# Mcu.net
KiCad netlist of a schematic drawn in Altium Designer
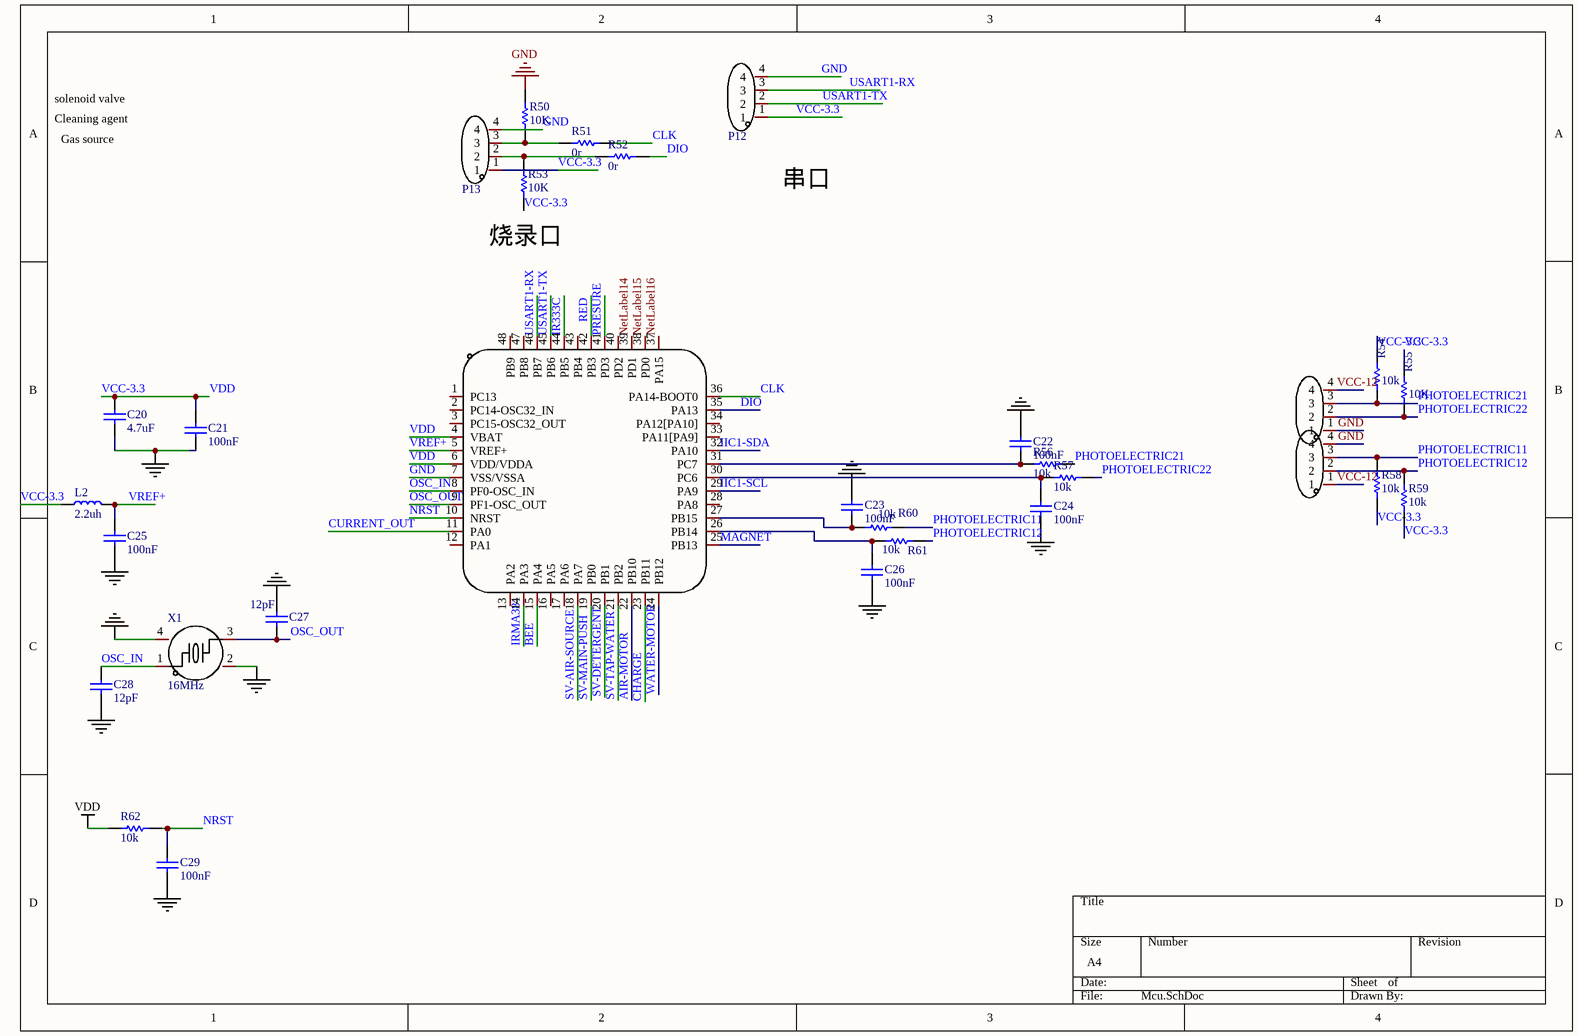
[diagram p0: Mcu.SchDoc]

(export (version "E")
  (design (tool "Eeschema 10.0.6"))
  (components
    (comp (ref "C20")
      (value "4.7uF")
      (footprint "zq:C0402")
      (fields (field (name "Comment") "CL05A475MP5NRNC") (field (name "PUBLISHER") "Altium Limited"))
      (libsource (lib "zq") (part "4.7uf"))
    )
    (comp (ref "C21")
      (value "100nF")
      (footprint "zq:C0402")
      (fields (field (name "Comment") "CL05B104KB54PNC") (field (name "PUBLISHER") "Altium Limited"))
      (libsource (lib "zq") (part "100nf"))
    )
    (comp (ref "C22")
      (value "100nF")
      (footprint "zq:C0402")
      (fields (field (name "Comment") "CL05B104KB54PNC") (field (name "PUBLISHER") "Altium Limited"))
      (libsource (lib "zq") (part "100nf"))
    )
    (comp (ref "C23")
      (value "100nF")
      (footprint "zq:C0402")
      (fields (field (name "Comment") "CL05B104KB54PNC") (field (name "PUBLISHER") "Altium Limited"))
      (libsource (lib "zq") (part "100nf"))
    )
    (comp (ref "C24")
      (value "100nF")
      (footprint "zq:C0402")
      (fields (field (name "Comment") "CL05B104KB54PNC") (field (name "PUBLISHER") "Altium Limited"))
      (libsource (lib "zq") (part "100nf"))
    )
    (comp (ref "C25")
      (value "100nF")
      (footprint "zq:C0402")
      (fields (field (name "Comment") "CL05B104KB54PNC") (field (name "PUBLISHER") "Altium Limited"))
      (libsource (lib "zq") (part "100nf"))
    )
    (comp (ref "C26")
      (value "100nF")
      (footprint "zq:C0402")
      (fields (field (name "Comment") "CL05B104KB54PNC") (field (name "PUBLISHER") "Altium Limited"))
      (libsource (lib "zq") (part "100nf"))
    )
    (comp (ref "C27")
      (value "12pF")
      (footprint "zq:C0402")
      (description "Capacitor")
      (fields (field (name "Comment") "0402CG120J500NT") (field (name "PUBLISHER") "Altium Limited"))
      (libsource (lib "zq") (part "cap"))
    )
    (comp (ref "C28")
      (value "12pF")
      (footprint "zq:C0402")
      (description "Capacitor")
      (fields (field (name "Comment") "0402CG120J500NT") (field (name "PUBLISHER") "Altium Limited"))
      (libsource (lib "zq") (part "cap"))
    )
    (comp (ref "C29")
      (value "100nF")
      (footprint "zq:C0402")
      (fields (field (name "Comment") "CL05B104KB54PNC") (field (name "PUBLISHER") "Altium Limited"))
      (libsource (lib "zq") (part "100nf"))
    )
    (comp (ref "L2")
      (value "2.2uh")
      (footprint "zq:L0603")
      (description "电感")
      (fields (field (name "Comment") "CMI160808U2R2KT"))
      (libsource (lib "zq") (part "inductance_small"))
    )
    (comp (ref "P12")
      (value "YTC-HAA200A-4A")
      (footprint "zq:CONN-TH_4P-P2.00_HCTL_HC-PH-4A-X")
      (description "4p")
      (fields (field (name "MANUFACTURER") "YIYUAN(怡远)"))
      (libsource (lib "zq") (part "ph 2.0"))
    )
    (comp (ref "P13")
      (value "YTC-HAA200A-4A")
      (footprint "zq:CONN-TH_4P-P2.00_HCTL_HC-PH-4A-X")
      (description "4p")
      (fields (field (name "MANUFACTURER") "YIYUAN(怡远)"))
      (libsource (lib "zq") (part "ph 2.0"))
    )
    (comp (ref "P14")
      (value "ZX-HY2.0-4PZZ")
      (footprint "zq:CONN-TH_4P-P2.00_HX20020-4A_2")
      (description "4p")
      (fields (field (name "MANUFACTURER") "Megastar(兆星)"))
      (libsource (lib "zq") (part "HY2.0-4PZZ"))
    )
    (comp (ref "P15")
      (value "ZX-HY2.0-4PZZ")
      (footprint "zq:CONN-TH_4P-P2.00_HX20020-4A_2")
      (description "4p")
      (fields (field (name "MANUFACTURER") "Megastar(兆星)"))
      (libsource (lib "zq") (part "HY2.0-4PZZ"))
    )
    (comp (ref "R50")
      (value "10K")
      (footprint "zq:R0402")
      (description "Semiconductor Resistor")
      (fields (field (name "Comment") "0402WGF1002TCE") (field (name "PUBLISHER") "Altium Limited"))
      (libsource (lib "zq") (part "10K"))
    )
    (comp (ref "R51")
      (value "0r")
      (footprint "zq:R0402")
      (fields (field (name "Comment") "0402WGF0000TCE") (field (name "PUBLISHER") "Altium Limited"))
      (libsource (lib "zq") (part "0r"))
    )
    (comp (ref "R52")
      (value "0r")
      (footprint "zq:R0402")
      (fields (field (name "Comment") "0402WGF0000TCE") (field (name "PUBLISHER") "Altium Limited"))
      (libsource (lib "zq") (part "0r"))
    )
    (comp (ref "R53")
      (value "10K")
      (footprint "zq:R0402")
      (description "Semiconductor Resistor")
      (fields (field (name "Comment") "0402WGF1002TCE") (field (name "PUBLISHER") "Altium Limited"))
      (libsource (lib "zq") (part "10K"))
    )
    (comp (ref "R54")
      (value "10k")
      (footprint "zq:R0402")
      (description "Semiconductor Resistor")
      (fields (field (name "Comment") "0402WGF1002TCE") (field (name "PUBLISHER") "Altium Limited"))
      (libsource (lib "zq") (part "Res Semi"))
    )
    (comp (ref "R55")
      (value "10K")
      (footprint "zq:R0402")
      (description "Semiconductor Resistor")
      (fields (field (name "Comment") "0402WGF1002TCE") (field (name "PUBLISHER") "Altium Limited"))
      (libsource (lib "zq") (part "Res Semi"))
    )
    (comp (ref "R56")
      (value "10k")
      (footprint "zq:R0402")
      (description "Semiconductor Resistor")
      (fields (field (name "Comment") "0402WGF1002TCE") (field (name "PUBLISHER") "Altium Limited"))
      (libsource (lib "zq") (part "Res Semi"))
    )
    (comp (ref "R57")
      (value "10k")
      (footprint "zq:R0402")
      (description "Semiconductor Resistor")
      (fields (field (name "Comment") "0402WGF1002TCE") (field (name "PUBLISHER") "Altium Limited"))
      (libsource (lib "zq") (part "Res Semi"))
    )
    (comp (ref "R58")
      (value "10k")
      (footprint "zq:R0402")
      (description "Semiconductor Resistor")
      (fields (field (name "Comment") "0402WGF1002TCE") (field (name "PUBLISHER") "Altium Limited"))
      (libsource (lib "zq") (part "Res Semi"))
    )
    (comp (ref "R59")
      (value "10k")
      (footprint "zq:R0402")
      (description "Semiconductor Resistor")
      (fields (field (name "Comment") "0402WGF1002TCE") (field (name "PUBLISHER") "Altium Limited"))
      (libsource (lib "zq") (part "Res Semi"))
    )
    (comp (ref "R60")
      (value "10k")
      (footprint "zq:R0402")
      (description "Semiconductor Resistor")
      (fields (field (name "Comment") "0402WGF1002TCE") (field (name "PUBLISHER") "Altium Limited"))
      (libsource (lib "zq") (part "Res Semi"))
    )
    (comp (ref "R61")
      (value "10k")
      (footprint "zq:R0402")
      (description "Semiconductor Resistor")
      (fields (field (name "Comment") "0402WGF1002TCE") (field (name "PUBLISHER") "Altium Limited"))
      (libsource (lib "zq") (part "Res Semi"))
    )
    (comp (ref "R62")
      (value "10k")
      (footprint "zq:R0402")
      (description "Semiconductor Resistor")
      (fields (field (name "Comment") "0402WGF1002TCE") (field (name "PUBLISHER") "Altium Limited"))
      (libsource (lib "zq") (part "Res Semi"))
    )
    (comp (ref "U4")
      (value "STM32G070CBT6")
      (footprint "zq:LQFP-48_L7.0-W7.0-P0.50-LS9.0-BL")
      (fields (field (name "MANUFACTURER") "ST(意法半导体)"))
      (libsource (lib "zq") (part "STM32G070CBT6"))
    )
    (comp (ref "X1")
      (value "X322516MLB4SI")
      (footprint "zq:CRYSTAL-SMD_4P-L3.2-W2.5-BL")
      (fields
        (field (name "MANUFACTURER") "YXC(扬兴晶振)")
        (field (name "MANUFACTURER PART") "XL7EL89COI-111YLC-16M")
        (field (name "NAME") "16MHz")
      )
      (libsource (lib "zq") (part "XL7EL89COI-111YLC-16M"))
    )
  )
  (nets
    (net (code "1") (name "/AIR-MOTOR") (class "Default")
      (node (ref "U4") (pin "22") (pinfunction "PB10_22") (pintype "passive"))
    )
    (net (code "2") (name "/BEE") (class "Default")
      (node (ref "U4") (pin "15") (pinfunction "PA4_15") (pintype "passive"))
    )
    (net (code "3") (name "/CHARGE") (class "Default")
      (node (ref "U4") (pin "23") (pinfunction "PB11_23") (pintype "passive"))
    )
    (net (code "4") (name "/CLK") (class "Default")
      (node (ref "R51") (pin "2") (pinfunction "2_2") (pintype "passive"))
      (node (ref "U4") (pin "36") (pinfunction "PA14-BOOT0_36") (pintype "passive"))
    )
    (net (code "5") (name "/CURRENT_OUT") (class "Default")
      (node (ref "U4") (pin "11") (pinfunction "PA0_11") (pintype "passive"))
    )
    (net (code "6") (name "/DIO") (class "Default")
      (node (ref "R52") (pin "2") (pinfunction "2_2") (pintype "passive"))
      (node (ref "U4") (pin "35") (pinfunction "PA13_35") (pintype "passive"))
    )
    (net (code "7") (name "/IIC1-SCL") (class "Default")
      (node (ref "U4") (pin "29") (pinfunction "PA9_29") (pintype "passive"))
    )
    (net (code "8") (name "/IIC1-SDA") (class "Default")
      (node (ref "U4") (pin "32") (pinfunction "PA10_32") (pintype "passive"))
    )
    (net (code "9") (name "/IR333C") (class "Default")
      (node (ref "U4") (pin "44") (pinfunction "PB5_44") (pintype "passive"))
    )
    (net (code "10") (name "/IRMA381") (class "Default")
      (node (ref "U4") (pin "14") (pinfunction "PA3_14") (pintype "passive"))
    )
    (net (code "11") (name "/MAGNET") (class "Default")
      (node (ref "U4") (pin "25") (pinfunction "PB13_25") (pintype "passive"))
    )
    (net (code "12") (name "/NRST") (class "Default")
      (node (ref "C29") (pin "1") (pinfunction "1_1") (pintype "passive"))
      (node (ref "R62") (pin "1") (pinfunction "1_1") (pintype "passive"))
      (node (ref "U4") (pin "10") (pinfunction "NRST_10") (pintype "passive"))
    )
    (net (code "13") (name "/NetLabel14") (class "Default")
      (node (ref "U4") (pin "39") (pinfunction "PD1_39") (pintype "passive"))
    )
    (net (code "14") (name "/NetLabel15") (class "Default")
      (node (ref "U4") (pin "38") (pinfunction "PD0_38") (pintype "passive"))
    )
    (net (code "15") (name "/NetLabel16") (class "Default")
      (node (ref "U4") (pin "37") (pinfunction "PA15_37") (pintype "passive"))
    )
    (net (code "16") (name "/OSC_IN") (class "Default")
      (node (ref "C28") (pin "2") (pinfunction "2_2") (pintype "passive"))
      (node (ref "U4") (pin "8") (pinfunction "PF0-OSC_IN_8") (pintype "passive"))
      (node (ref "X1") (pin "1") (pinfunction "1_1") (pintype "passive"))
    )
    (net (code "17") (name "/OSC_OUT") (class "Default")
      (node (ref "C27") (pin "1") (pinfunction "1_1") (pintype "passive"))
      (node (ref "U4") (pin "9") (pinfunction "PF1-OSC_OUT_9") (pintype "passive"))
      (node (ref "X1") (pin "3") (pinfunction "3_3") (pintype "passive"))
    )
    (net (code "18") (name "/PHOTOELECTRIC11") (class "Default")
      (node (ref "P15") (pin "3") (pinfunction "3_3") (pintype "passive"))
      (node (ref "R58") (pin "2") (pinfunction "2_2") (pintype "passive"))
      (node (ref "R60") (pin "2") (pinfunction "2_2") (pintype "passive"))
    )
    (net (code "19") (name "/PHOTOELECTRIC12") (class "Default")
      (node (ref "P15") (pin "2") (pinfunction "2_2") (pintype "passive"))
      (node (ref "R59") (pin "2") (pinfunction "2_2") (pintype "passive"))
      (node (ref "R61") (pin "2") (pinfunction "2_2") (pintype "passive"))
    )
    (net (code "20") (name "/PHOTOELECTRIC21") (class "Default")
      (node (ref "P14") (pin "3") (pinfunction "3_3") (pintype "passive"))
      (node (ref "R54") (pin "2") (pinfunction "2_2") (pintype "passive"))
      (node (ref "R56") (pin "2") (pinfunction "2_2") (pintype "passive"))
    )
    (net (code "21") (name "/PHOTOELECTRIC22") (class "Default")
      (node (ref "P14") (pin "2") (pinfunction "2_2") (pintype "passive"))
      (node (ref "R55") (pin "2") (pinfunction "2_2") (pintype "passive"))
      (node (ref "R57") (pin "2") (pinfunction "2_2") (pintype "passive"))
    )
    (net (code "22") (name "/PRESURE") (class "Default")
      (node (ref "U4") (pin "41") (pinfunction "PD3_41") (pintype "passive"))
    )
    (net (code "23") (name "/RED") (class "Default")
      (node (ref "U4") (pin "42") (pinfunction "PB3_42") (pintype "passive"))
    )
    (net (code "24") (name "/SV-AIR-SOURCE") (class "Default")
      (node (ref "U4") (pin "18") (pinfunction "PA7_18") (pintype "passive"))
    )
    (net (code "25") (name "/SV-DETERGENT") (class "Default")
      (node (ref "U4") (pin "20") (pinfunction "PB1_20") (pintype "passive"))
    )
    (net (code "26") (name "/SV-MAIN-PUSH") (class "Default")
      (node (ref "U4") (pin "19") (pinfunction "PB0_19") (pintype "passive"))
    )
    (net (code "27") (name "/SV-TAP-WATER") (class "Default")
      (node (ref "U4") (pin "21") (pinfunction "PB2_21") (pintype "passive"))
    )
    (net (code "28") (name "/USART1-RX") (class "Default")
      (node (ref "P12") (pin "3") (pinfunction "3_3") (pintype "passive"))
      (node (ref "U4") (pin "46") (pinfunction "PB7_46") (pintype "passive"))
    )
    (net (code "29") (name "/USART1-TX") (class "Default")
      (node (ref "P12") (pin "2") (pinfunction "2_2") (pintype "passive"))
      (node (ref "U4") (pin "45") (pinfunction "PB6_45") (pintype "passive"))
    )
    (net (code "30") (name "/VCC-12") (class "Default")
      (node (ref "P14") (pin "4") (pinfunction "4_4") (pintype "passive"))
      (node (ref "P15") (pin "1") (pinfunction "1_1") (pintype "passive"))
    )
    (net (code "31") (name "/VREF+") (class "Default")
      (node (ref "C25") (pin "1") (pinfunction "1_1") (pintype "passive"))
      (node (ref "L2") (pin "2") (pinfunction "2_2") (pintype "passive"))
      (node (ref "U4") (pin "5") (pinfunction "VREF+_5") (pintype "passive"))
    )
    (net (code "32") (name "/WATER-MOTOR") (class "Default")
      (node (ref "U4") (pin "24") (pinfunction "PB12_24") (pintype "passive"))
    )
    (net (code "33") (name "GND") (class "Default")
      (node (ref "C20") (pin "2") (pinfunction "2_2") (pintype "passive"))
      (node (ref "C21") (pin "2") (pinfunction "2_2") (pintype "passive"))
      (node (ref "C22") (pin "1") (pinfunction "1_1") (pintype "passive"))
      (node (ref "C23") (pin "1") (pinfunction "1_1") (pintype "passive"))
      (node (ref "C24") (pin "2") (pinfunction "2_2") (pintype "passive"))
      (node (ref "C25") (pin "2") (pinfunction "2_2") (pintype "passive"))
      (node (ref "C26") (pin "2") (pinfunction "2_2") (pintype "passive"))
      (node (ref "C27") (pin "2") (pinfunction "2_2") (pintype "passive"))
      (node (ref "C28") (pin "1") (pinfunction "1_1") (pintype "passive"))
      (node (ref "C29") (pin "2") (pinfunction "2_2") (pintype "passive"))
      (node (ref "P12") (pin "4") (pinfunction "4_4") (pintype "passive"))
      (node (ref "P13") (pin "4") (pinfunction "4_4") (pintype "passive"))
      (node (ref "P14") (pin "1") (pinfunction "1_1") (pintype "passive"))
      (node (ref "P15") (pin "4") (pinfunction "4_4") (pintype "passive"))
      (node (ref "R50") (pin "2") (pinfunction "2_2") (pintype "passive"))
      (node (ref "U4") (pin "7") (pinfunction "VSS/VSSA_7") (pintype "passive"))
      (node (ref "X1") (pin "2") (pinfunction "GND_2") (pintype "passive"))
      (node (ref "X1") (pin "4") (pinfunction "GND_4") (pintype "passive"))
    )
    (net (code "34") (name "Net-(P13-Pad2)") (class "Default")
      (node (ref "P13") (pin "2") (pinfunction "2_2") (pintype "passive"))
      (node (ref "R52") (pin "1") (pinfunction "1_1") (pintype "passive"))
      (node (ref "R53") (pin "2") (pinfunction "2_2") (pintype "passive"))
    )
    (net (code "35") (name "Net-(P13-Pad3)") (class "Default")
      (node (ref "P13") (pin "3") (pinfunction "3_3") (pintype "passive"))
      (node (ref "R50") (pin "1") (pinfunction "1_1") (pintype "passive"))
      (node (ref "R51") (pin "1") (pinfunction "1_1") (pintype "passive"))
    )
    (net (code "36") (name "Net-(U4-PB14)") (class "Default")
      (node (ref "C26") (pin "1") (pinfunction "1_1") (pintype "passive"))
      (node (ref "R61") (pin "1") (pinfunction "1_1") (pintype "passive"))
      (node (ref "U4") (pin "26") (pinfunction "PB14_26") (pintype "passive"))
    )
    (net (code "37") (name "Net-(U4-PB15)") (class "Default")
      (node (ref "C23") (pin "2") (pinfunction "2_2") (pintype "passive"))
      (node (ref "R60") (pin "1") (pinfunction "1_1") (pintype "passive"))
      (node (ref "U4") (pin "27") (pinfunction "PB15_27") (pintype "passive"))
    )
    (net (code "38") (name "Net-(U4-PC6)") (class "Default")
      (node (ref "C24") (pin "1") (pinfunction "1_1") (pintype "passive"))
      (node (ref "R57") (pin "1") (pinfunction "1_1") (pintype "passive"))
      (node (ref "U4") (pin "30") (pinfunction "PC6_30") (pintype "passive"))
    )
    (net (code "39") (name "Net-(U4-PC7)") (class "Default")
      (node (ref "C22") (pin "2") (pinfunction "2_2") (pintype "passive"))
      (node (ref "R56") (pin "1") (pinfunction "1_1") (pintype "passive"))
      (node (ref "U4") (pin "31") (pinfunction "PC7_31") (pintype "passive"))
    )
    (net (code "40") (name "VDD") (class "Default")
      (node (ref "C20") (pin "1") (pinfunction "1_1") (pintype "passive"))
      (node (ref "C21") (pin "1") (pinfunction "1_1") (pintype "passive"))
      (node (ref "L2") (pin "1") (pinfunction "1_1") (pintype "passive"))
      (node (ref "P12") (pin "1") (pinfunction "1_1") (pintype "passive"))
      (node (ref "P13") (pin "1") (pinfunction "1_1") (pintype "passive"))
      (node (ref "R53") (pin "1") (pinfunction "1_1") (pintype "passive"))
      (node (ref "R54") (pin "1") (pinfunction "1_1") (pintype "passive"))
      (node (ref "R55") (pin "1") (pinfunction "1_1") (pintype "passive"))
      (node (ref "R58") (pin "1") (pinfunction "1_1") (pintype "passive"))
      (node (ref "R59") (pin "1") (pinfunction "1_1") (pintype "passive"))
      (node (ref "R62") (pin "2") (pinfunction "2_2") (pintype "passive"))
      (node (ref "U4") (pin "4") (pinfunction "VBAT_4") (pintype "passive"))
      (node (ref "U4") (pin "6") (pinfunction "VDD/VDDA_6") (pintype "passive"))
    )
    (net (code "41") (name "unconnected-(U4-PA1-Pad12)") (class "Default")
      (node (ref "U4") (pin "12") (pinfunction "PA1_12") (pintype "passive"))
    )
    (net (code "42") (name "unconnected-(U4-PA2-Pad13)") (class "Default")
      (node (ref "U4") (pin "13") (pinfunction "PA2_13") (pintype "passive"))
    )
    (net (code "43") (name "unconnected-(U4-PA5-Pad16)") (class "Default")
      (node (ref "U4") (pin "16") (pinfunction "PA5_16") (pintype "passive"))
    )
    (net (code "44") (name "unconnected-(U4-PA6-Pad17)") (class "Default")
      (node (ref "U4") (pin "17") (pinfunction "PA6_17") (pintype "passive"))
    )
    (net (code "45") (name "unconnected-(U4-PA8-Pad28)") (class "Default")
      (node (ref "U4") (pin "28") (pinfunction "PA8_28") (pintype "passive"))
    )
    (net (code "46") (name "unconnected-(U4-PA11[PA9]-Pad33)") (class "Default")
      (node (ref "U4") (pin "33") (pinfunction "PA11[PA9]_33") (pintype "passive"))
    )
    (net (code "47") (name "unconnected-(U4-PA12[PA10]-Pad34)") (class "Default")
      (node (ref "U4") (pin "34") (pinfunction "PA12[PA10]_34") (pintype "passive"))
    )
    (net (code "48") (name "unconnected-(U4-PB4-Pad43)") (class "Default")
      (node (ref "U4") (pin "43") (pinfunction "PB4_43") (pintype "passive"))
    )
    (net (code "49") (name "unconnected-(U4-PB8-Pad47)") (class "Default")
      (node (ref "U4") (pin "47") (pinfunction "PB8_47") (pintype "passive"))
    )
    (net (code "50") (name "unconnected-(U4-PB9-Pad48)") (class "Default")
      (node (ref "U4") (pin "48") (pinfunction "PB9_48") (pintype "passive"))
    )
    (net (code "51") (name "unconnected-(U4-PC13-Pad1)") (class "Default")
      (node (ref "U4") (pin "1") (pinfunction "PC13_1") (pintype "passive"))
    )
    (net (code "52") (name "unconnected-(U4-PC14-OSC32_IN-Pad2)") (class "Default")
      (node (ref "U4") (pin "2") (pinfunction "PC14-OSC32_IN_2") (pintype "passive"))
    )
    (net (code "53") (name "unconnected-(U4-PC15-OSC32_OUT-Pad3)") (class "Default")
      (node (ref "U4") (pin "3") (pinfunction "PC15-OSC32_OUT_3") (pintype "passive"))
    )
    (net (code "54") (name "unconnected-(U4-PD2-Pad40)") (class "Default")
      (node (ref "U4") (pin "40") (pinfunction "PD2_40") (pintype "passive"))
    )
  )
)
